# LMS7002M_RF2.net
KiCad netlist of a schematic drawn in Altium Designer
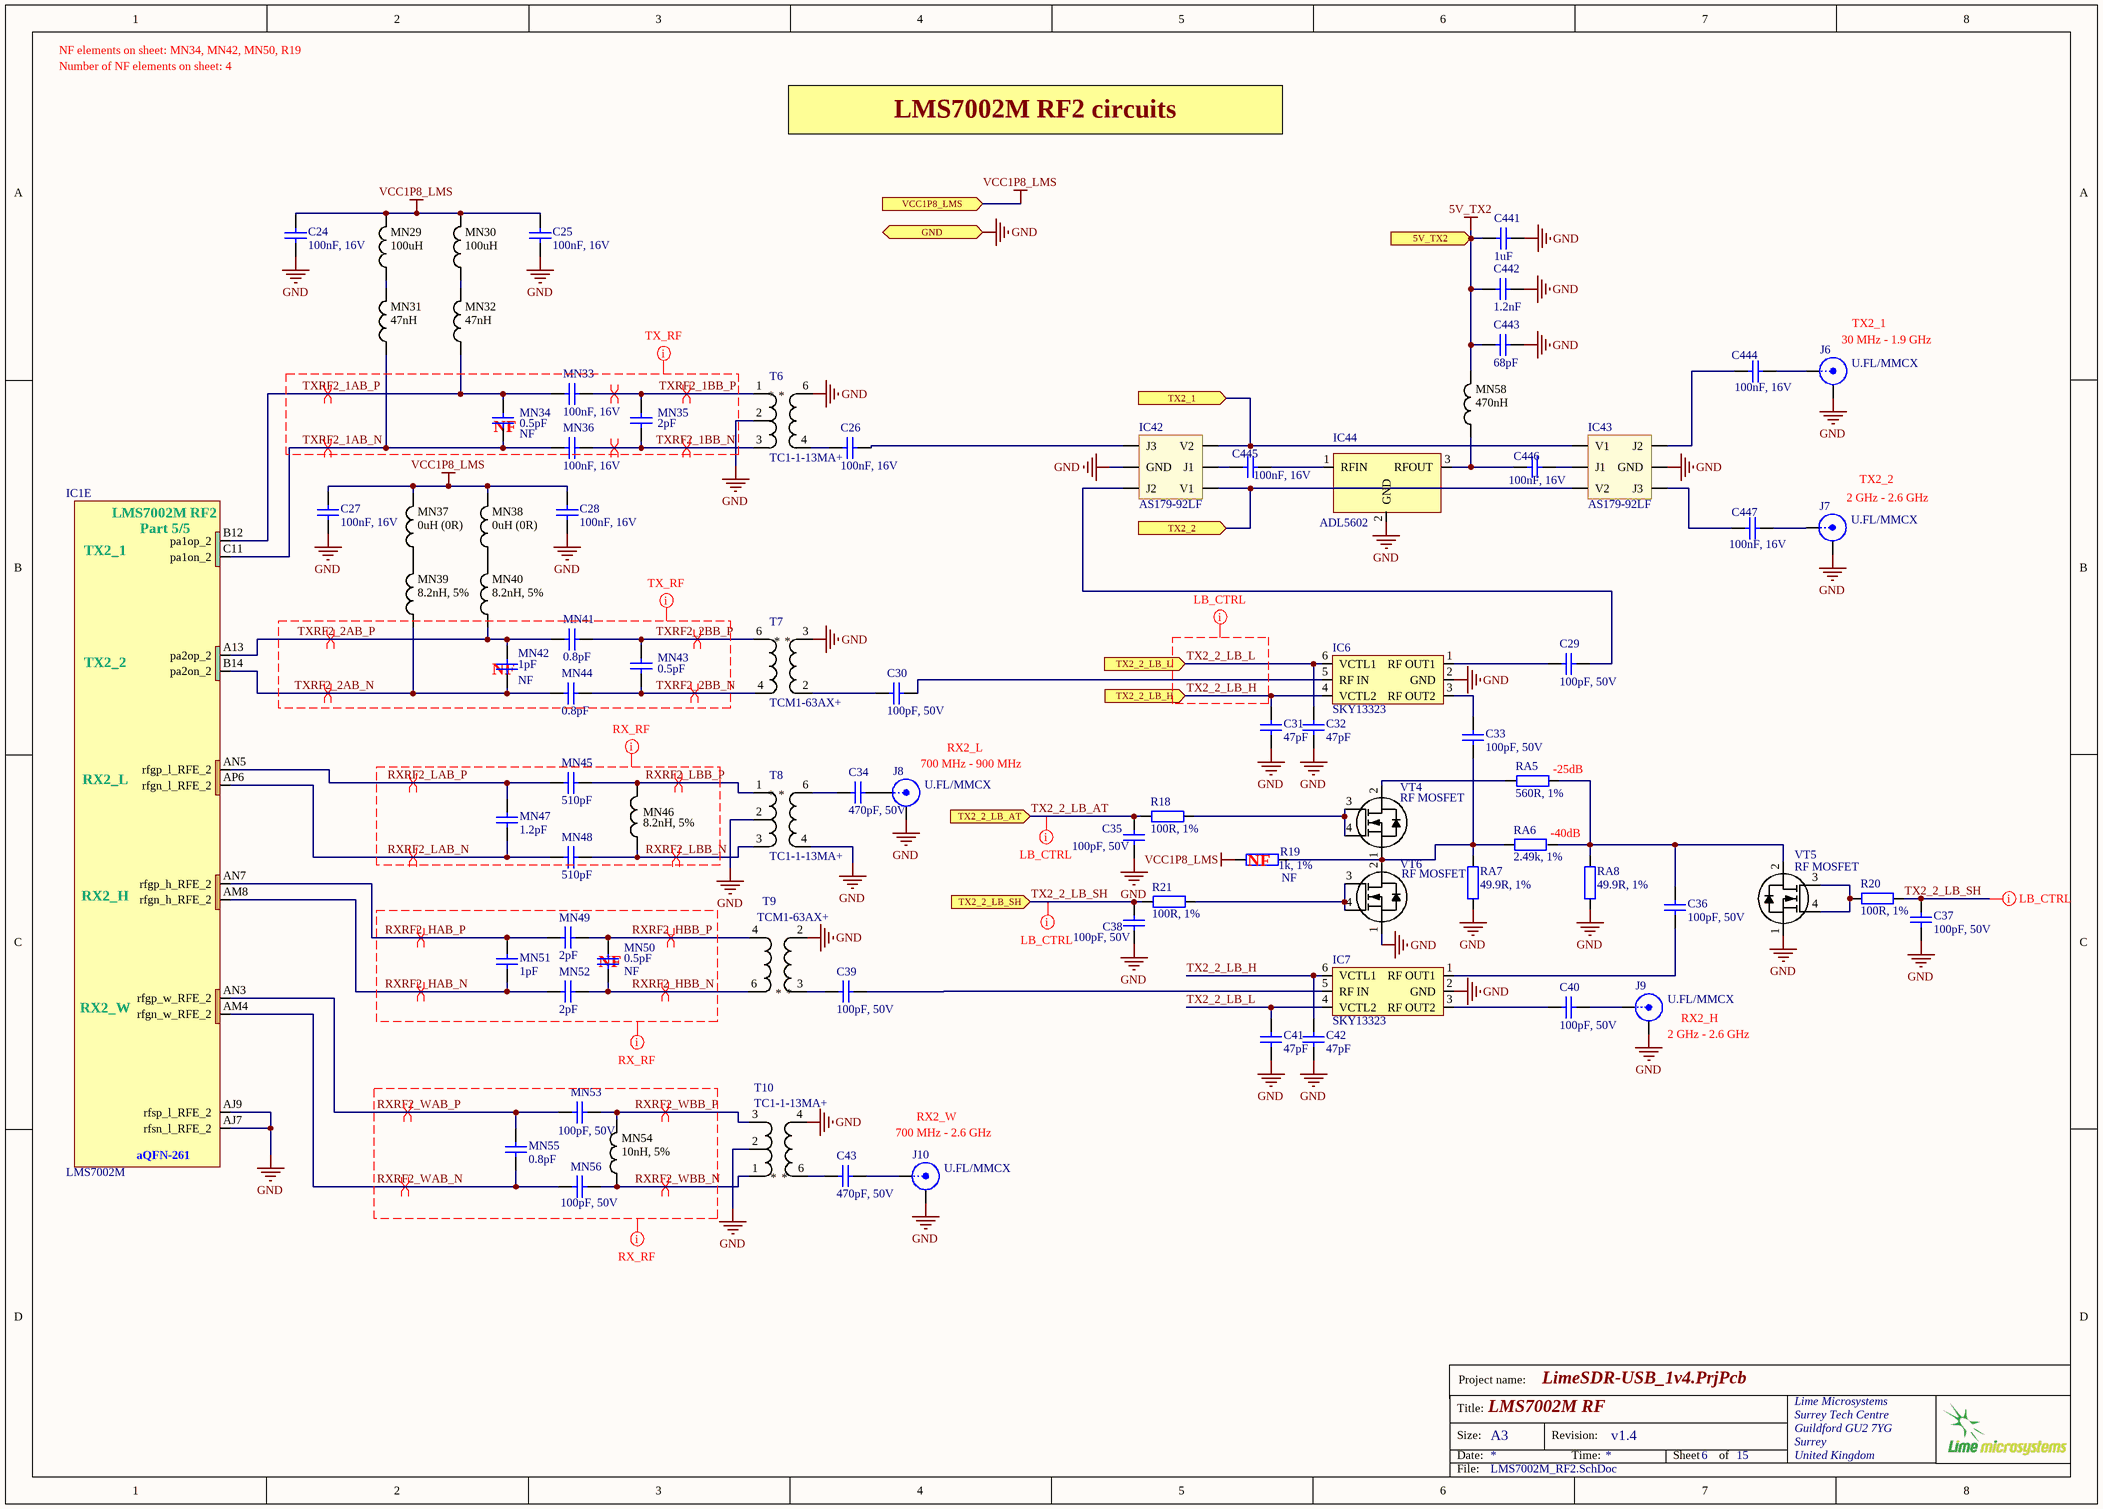
[diagram p0: LMS7002M_RF2.SchDoc]

(export (version "E")
  (design (tool "Eeschema 10.0.6"))
  (components
    (comp (ref "C24")
      (value "100nF, 16V")
      (footprint "CAP0402")
      (fields
        (field (name "MANUFACTURER") "Murata Electronics")
        (field (name "TOLERANCE") "10 %")
        (field (name "MANUFACTURER PART NUMBER") "GRM155R71C104KA88D")
      )
      (libsource (lib "LimeMicroAltiumLib_schLib") (part "Cap_0402"))
    )
    (comp (ref "C25")
      (value "100nF, 16V")
      (footprint "CAP0402")
      (fields
        (field (name "MANUFACTURER") "Murata Electronics")
        (field (name "TOLERANCE") "10 %")
        (field (name "MANUFACTURER PART NUMBER") "GRM155R71C104KA88D")
      )
      (libsource (lib "LimeMicroAltiumLib_schLib") (part "Cap_0402"))
    )
    (comp (ref "C26")
      (value "100nF, 16V")
      (footprint "CAP0402")
      (fields
        (field (name "MANUFACTURER") "Murata Electronics")
        (field (name "TOLERANCE") "10 %")
        (field (name "MANUFACTURER PART NUMBER") "GRM155R71C104KA88D")
      )
      (libsource (lib "LimeMicroAltiumLib_schLib") (part "Cap_0402"))
    )
    (comp (ref "C27")
      (value "100nF, 16V")
      (footprint "CAP0402")
      (fields
        (field (name "MANUFACTURER") "Murata Electronics")
        (field (name "TOLERANCE") "10 %")
        (field (name "MANUFACTURER PART NUMBER") "GRM155R71C104KA88D")
      )
      (libsource (lib "LimeMicroAltiumLib_schLib") (part "Cap_0402"))
    )
    (comp (ref "C28")
      (value "100nF, 16V")
      (footprint "CAP0402")
      (fields
        (field (name "MANUFACTURER") "Murata Electronics")
        (field (name "TOLERANCE") "10 %")
        (field (name "MANUFACTURER PART NUMBER") "GRM155R71C104KA88D")
      )
      (libsource (lib "LimeMicroAltiumLib_schLib") (part "Cap_0402"))
    )
    (comp (ref "C29")
      (value "100pF, 50V")
      (footprint "CAP0402")
      (fields (field (name "TOLERANCE") "±5%") (field (name "MANUFACTURER") "Yageo"))
      (libsource (lib "LimeMicroAltiumLib_schLib") (part "Cap_0402"))
    )
    (comp (ref "C30")
      (value "100pF, 50V")
      (footprint "CAP0402")
      (fields (field (name "TOLERANCE") "±5%") (field (name "MANUFACTURER") "Yageo"))
      (libsource (lib "LimeMicroAltiumLib_schLib") (part "Cap_0402"))
    )
    (comp (ref "C31")
      (value "47pF")
      (footprint "CAP0402")
      (fields (field (name "TOLERANCE") "±1%") (field (name "MANUFACTURER") "TDK Corporation"))
      (libsource (lib "LimeMicroAltiumLib_schLib") (part "Cap_0402"))
    )
    (comp (ref "C32")
      (value "47pF")
      (footprint "CAP0402")
      (fields (field (name "TOLERANCE") "±1%") (field (name "MANUFACTURER") "TDK Corporation"))
      (libsource (lib "LimeMicroAltiumLib_schLib") (part "Cap_0402"))
    )
    (comp (ref "C33")
      (value "100pF, 50V")
      (footprint "CAP0402")
      (fields (field (name "TOLERANCE") "±5%") (field (name "MANUFACTURER") "Yageo"))
      (libsource (lib "LimeMicroAltiumLib_schLib") (part "Cap_0402"))
    )
    (comp (ref "C34")
      (value "470pF, 50V")
      (footprint "CAP0402")
      (fields
        (field (name "MANUFACTURER PART NUMBER") "C1005C0G1H471J050BA")
        (field (name "TOLERANCE") "±5%")
        (field (name "MANUFACTURER") "TDK Corporation")
      )
      (libsource (lib "LimeMicroAltiumLib_schLib") (part "Cap_0402"))
    )
    (comp (ref "C35")
      (value "100pF, 50V")
      (footprint "CAP0402")
      (fields (field (name "TOLERANCE") "±5%") (field (name "MANUFACTURER") "Yageo"))
      (libsource (lib "LimeMicroAltiumLib_schLib") (part "Cap_0402"))
    )
    (comp (ref "C36")
      (value "100pF, 50V")
      (footprint "CAP0402")
      (fields (field (name "TOLERANCE") "±5%") (field (name "MANUFACTURER") "Yageo"))
      (libsource (lib "LimeMicroAltiumLib_schLib") (part "Cap_0402"))
    )
    (comp (ref "C37")
      (value "100pF, 50V")
      (footprint "CAP0402")
      (fields (field (name "TOLERANCE") "±5%") (field (name "MANUFACTURER") "Yageo"))
      (libsource (lib "LimeMicroAltiumLib_schLib") (part "Cap_0402"))
    )
    (comp (ref "C38")
      (value "100pF, 50V")
      (footprint "CAP0402")
      (fields (field (name "TOLERANCE") "±5%") (field (name "MANUFACTURER") "Yageo"))
      (libsource (lib "LimeMicroAltiumLib_schLib") (part "Cap_0402"))
    )
    (comp (ref "C39")
      (value "100pF, 50V")
      (footprint "CAP0402")
      (fields (field (name "TOLERANCE") "±5%") (field (name "MANUFACTURER") "Yageo"))
      (libsource (lib "LimeMicroAltiumLib_schLib") (part "Cap_0402"))
    )
    (comp (ref "C40")
      (value "100pF, 50V")
      (footprint "CAP0402")
      (fields (field (name "TOLERANCE") "±5%") (field (name "MANUFACTURER") "Yageo"))
      (libsource (lib "LimeMicroAltiumLib_schLib") (part "Cap_0402"))
    )
    (comp (ref "C41")
      (value "47pF")
      (footprint "CAP0402")
      (fields (field (name "TOLERANCE") "±1%") (field (name "MANUFACTURER") "TDK Corporation"))
      (libsource (lib "LimeMicroAltiumLib_schLib") (part "Cap_0402"))
    )
    (comp (ref "C42")
      (value "47pF")
      (footprint "CAP0402")
      (fields (field (name "TOLERANCE") "±1%") (field (name "MANUFACTURER") "TDK Corporation"))
      (libsource (lib "LimeMicroAltiumLib_schLib") (part "Cap_0402"))
    )
    (comp (ref "C43")
      (value "470pF, 50V")
      (footprint "CAP0402")
      (fields
        (field (name "MANUFACTURER PART NUMBER") "C1005C0G1H471J050BA")
        (field (name "TOLERANCE") "±5%")
        (field (name "MANUFACTURER") "TDK Corporation")
      )
      (libsource (lib "LimeMicroAltiumLib_schLib") (part "Cap_0402"))
    )
    (comp (ref "C441")
      (value "1uF")
      (footprint "CAP0402")
      (fields
        (field (name "MANUFACTURER") "Murata Electronics")
        (field (name "TOLERANCE") "10 %")
        (field (name "MANUFACTURER PART NUMBER") "GRM155R71C104KA88D")
      )
      (libsource (lib "LimeMicroAltiumLib_schLib") (part "Cap_0402"))
    )
    (comp (ref "C442")
      (value "1.2nF")
      (footprint "CAP0402")
      (fields
        (field (name "MANUFACTURER") "Murata Electronics")
        (field (name "TOLERANCE") "10 %")
        (field (name "MANUFACTURER PART NUMBER") "GRM155R71C104KA88D")
      )
      (libsource (lib "LimeMicroAltiumLib_schLib") (part "Cap_0402"))
    )
    (comp (ref "C443")
      (value "68pF")
      (footprint "CAP0402")
      (fields
        (field (name "MANUFACTURER") "Murata Electronics")
        (field (name "TOLERANCE") "10 %")
        (field (name "MANUFACTURER PART NUMBER") "GRM155R71C104KA88D")
      )
      (libsource (lib "LimeMicroAltiumLib_schLib") (part "Cap_0402"))
    )
    (comp (ref "C444")
      (value "100nF, 16V")
      (footprint "CAP0402")
      (fields
        (field (name "MANUFACTURER") "Murata Electronics")
        (field (name "TOLERANCE") "10 %")
        (field (name "MANUFACTURER PART NUMBER") "GRM155R71C104KA88D")
      )
      (libsource (lib "LimeMicroAltiumLib_schLib") (part "Cap_0402"))
    )
    (comp (ref "C445")
      (value "100nF, 16V")
      (footprint "CAP0402")
      (fields
        (field (name "MANUFACTURER") "Murata Electronics")
        (field (name "TOLERANCE") "10 %")
        (field (name "MANUFACTURER PART NUMBER") "GRM155R71C104KA88D")
      )
      (libsource (lib "LimeMicroAltiumLib_schLib") (part "Cap_0402"))
    )
    (comp (ref "C446")
      (value "100nF, 16V")
      (footprint "CAP0402")
      (fields
        (field (name "MANUFACTURER") "Murata Electronics")
        (field (name "TOLERANCE") "10 %")
        (field (name "MANUFACTURER PART NUMBER") "GRM155R71C104KA88D")
      )
      (libsource (lib "LimeMicroAltiumLib_schLib") (part "Cap_0402"))
    )
    (comp (ref "C447")
      (value "100nF, 16V")
      (footprint "CAP0402")
      (fields
        (field (name "MANUFACTURER") "Murata Electronics")
        (field (name "TOLERANCE") "10 %")
        (field (name "MANUFACTURER PART NUMBER") "GRM155R71C104KA88D")
      )
      (libsource (lib "LimeMicroAltiumLib_schLib") (part "Cap_0402"))
    )
    (comp (ref "IC1")
      (value "LMS7002M")
      (footprint "LMS7002M_v3")
      (fields (field (name "MANUFACTURER") "Lime Microsystems"))
      (libsource (lib "LimeMicroAltiumLib_schLib") (part "LMS7002M"))
    )
    (comp (ref "IC6")
      (value "SKY13323")
      (footprint "SKY13323-378LF")
      (description "SKY13323-378LF: 0.1-3.0 GHz GaAs SPDT Switch")
      (fields (field (name "MANUFACTURER") "Skyworks Solutions Inc."))
      (libsource (lib "LimeMicroAltiumLib_schLib") (part "SKY13323"))
    )
    (comp (ref "IC7")
      (value "SKY13323")
      (footprint "SKY13323-378LF")
      (description "SKY13323-378LF: 0.1-3.0 GHz GaAs SPDT Switch")
      (fields (field (name "MANUFACTURER") "Skyworks Solutions Inc."))
      (libsource (lib "LimeMicroAltiumLib_schLib") (part "SKY13323"))
    )
    (comp (ref "IC42") (value "AS179-92LF") (footprint "SC-70") (libsource (lib "") (part "AS179-92LF_1")))
    (comp (ref "IC43")
      (value "AS179-92LF")
      (footprint "SC-70")
      (libsource (lib "LimeMicroAltiumLib_schLib") (part "AS179-92LF"))
    )
    (comp (ref "IC44")
      (value "ADL5602")
      (footprint "SOT-89-ADI-RK-3_M")
      (description "50 MHz to 4.0 GHz RF/IF Gain Block")
      (fields
        (field (name "MANUFACTURER") "Analog Devices Inc.")
        (field (name "MANUFACTURER PART NUMBER") "ADL5602ARKZ-R7")
      )
      (libsource (lib "LimeMicroAltiumLib_schLib") (part "ADL5602"))
    )
    (comp (ref "J6")
      (value "U.FL/MMCX")
      (footprint "MMCX_UFL_conn_u")
      (description "CONN UMC RCPT STR 50 OHM SMD")
      (fields (field (name "MANUFACTURER") "Molex, LLC"))
      (libsource (lib "LimeMicroAltiumLib_schLib") (part "RF_IF_connector"))
    )
    (comp (ref "J7")
      (value "U.FL/MMCX")
      (footprint "MMCX_UFL_conn_u")
      (description "CONN UMC RCPT STR 50 OHM SMD")
      (fields (field (name "MANUFACTURER") "Molex, LLC"))
      (libsource (lib "LimeMicroAltiumLib_schLib") (part "RF_IF_connector"))
    )
    (comp (ref "J8")
      (value "U.FL/MMCX")
      (footprint "MMCX_UFL_conn_u")
      (description "CONN UMC RCPT STR 50 OHM SMD")
      (fields (field (name "MANUFACTURER") "Molex, LLC"))
      (libsource (lib "LimeMicroAltiumLib_schLib") (part "RF_IF_connector"))
    )
    (comp (ref "J9")
      (value "U.FL/MMCX")
      (footprint "MMCX_UFL_conn_u")
      (description "CONN UMC RCPT STR 50 OHM SMD")
      (fields (field (name "MANUFACTURER") "Molex, LLC"))
      (libsource (lib "LimeMicroAltiumLib_schLib") (part "RF_IF_connector"))
    )
    (comp (ref "J10")
      (value "U.FL/MMCX")
      (footprint "MMCX_UFL_conn_u")
      (description "CONN UMC RCPT STR 50 OHM SMD")
      (fields (field (name "MANUFACTURER") "Molex, LLC"))
      (libsource (lib "LimeMicroAltiumLib_schLib") (part "RF_IF_connector"))
    )
    (comp (ref "MN29")
      (value "100uH")
      (footprint "RES0805")
      (fields
        (field (name "TOLERANCE") "±10%")
        (field (name "MANUFACTURER") "TDK Corporation")
        (field (name "MANUFACTURER PART NUMBER") "MLF2012C101KT000")
      )
      (libsource (lib "LimeMicroAltiumLib_schLib") (part "Inductor_0603"))
    )
    (comp (ref "MN30")
      (value "100uH")
      (footprint "RES0805")
      (fields
        (field (name "TOLERANCE") "±10%")
        (field (name "MANUFACTURER") "TDK Corporation")
        (field (name "MANUFACTURER PART NUMBER") "MLF2012C101KT000")
      )
      (libsource (lib "LimeMicroAltiumLib_schLib") (part "Inductor_0603"))
    )
    (comp (ref "MN31")
      (value "47nH")
      (footprint "RES0402")
      (fields
        (field (name "MANUFACTURER") "COILCRAFT")
        (field (name "MANUFACTURER PART NUMBER") "0402HP-47NXJLU")
      )
      (libsource (lib "LimeMicroAltiumLib_schLib") (part "Inductor_0603"))
    )
    (comp (ref "MN32")
      (value "47nH")
      (footprint "RES0402")
      (fields
        (field (name "MANUFACTURER") "COILCRAFT")
        (field (name "MANUFACTURER PART NUMBER") "0402HP-47NXJLU")
      )
      (libsource (lib "LimeMicroAltiumLib_schLib") (part "Inductor_0603"))
    )
    (comp (ref "MN33")
      (value "100nF, 16V")
      (footprint "CAP0402")
      (fields
        (field (name "MANUFACTURER") "Murata Electronics")
        (field (name "TOLERANCE") "10 %")
        (field (name "MANUFACTURER PART NUMBER") "GRM155R71C104KA88D")
      )
      (libsource (lib "LimeMicroAltiumLib_schLib") (part "Cap_0402"))
    )
    (comp (ref "MN34")
      (value "0.5pF")
      (footprint "CAP0402")
      (fields
        (field (name "ASSEMBLY INFO") "NF")
        (field (name "TOLERANCE") "±0.25pF")
        (field (name "MANUFACTURER") "Yageo")
      )
      (libsource (lib "LimeMicroAltiumLib_schLib") (part "Cap_0402"))
    )
    (comp (ref "MN35")
      (value "2pF")
      (footprint "CAP0402")
      (fields (field (name "MANUFACTURER PART NUMBER") "04025U2R0BAT2A") (field (name "MANUFACTURER") "AVX"))
      (libsource (lib "LimeMicroAltiumLib_schLib") (part "Cap_0402"))
    )
    (comp (ref "MN36")
      (value "100nF, 16V")
      (footprint "CAP0402")
      (fields
        (field (name "MANUFACTURER") "Murata Electronics")
        (field (name "TOLERANCE") "10 %")
        (field (name "MANUFACTURER PART NUMBER") "GRM155R71C104KA88D")
      )
      (libsource (lib "LimeMicroAltiumLib_schLib") (part "Cap_0402"))
    )
    (comp (ref "MN37")
      (value "0uH (0R)")
      (footprint "RES0805")
      (fields (field (name "MANUFACTURER") "BOURNS"))
      (libsource (lib "LimeMicroAltiumLib_schLib") (part "Inductor_0603"))
    )
    (comp (ref "MN38")
      (value "0uH (0R)")
      (footprint "RES0805")
      (fields (field (name "MANUFACTURER") "BOURNS"))
      (libsource (lib "LimeMicroAltiumLib_schLib") (part "Inductor_0603"))
    )
    (comp (ref "MN39")
      (value "8.2nH, 5%")
      (footprint "RES0402")
      (fields (field (name "MANUFACTURER") "COILCRAFT"))
      (libsource (lib "LimeMicroAltiumLib_schLib") (part "Inductor_0603"))
    )
    (comp (ref "MN40")
      (value "8.2nH, 5%")
      (footprint "RES0402")
      (fields (field (name "MANUFACTURER") "COILCRAFT"))
      (libsource (lib "LimeMicroAltiumLib_schLib") (part "Inductor_0603"))
    )
    (comp (ref "MN41")
      (value "0.8pF")
      (footprint "CAP0402")
      (fields
        (field (name "TOLERANCE") "±0.1pF")
        (field (name "MANUFACTURER") "Murata Electronics North America")
        (field (name "MANUFACTURER PART NUMBER") "GRM1555C1HR80BA01D")
      )
      (libsource (lib "LimeMicroAltiumLib_schLib") (part "Cap_0402"))
    )
    (comp (ref "MN42")
      (value "1pF")
      (footprint "CAP0402")
      (fields
        (field (name "ASSEMBLY INFO") "NF")
        (field (name "MANUFACTURER") "TDK Corporation")
        (field (name "TOLERANCE") "±0.1pF")
      )
      (libsource (lib "LimeMicroAltiumLib_schLib") (part "Cap_0402"))
    )
    (comp (ref "MN43")
      (value "0.5pF")
      (footprint "CAP0402")
      (fields (field (name "TOLERANCE") "±0.25pF") (field (name "MANUFACTURER") "Yageo"))
      (libsource (lib "LimeMicroAltiumLib_schLib") (part "Cap_0402"))
    )
    (comp (ref "MN44")
      (value "0.8pF")
      (footprint "CAP0402")
      (fields
        (field (name "TOLERANCE") "±0.1pF")
        (field (name "MANUFACTURER") "Murata Electronics North America")
        (field (name "MANUFACTURER PART NUMBER") "GRM1555C1HR80BA01D")
      )
      (libsource (lib "LimeMicroAltiumLib_schLib") (part "Cap_0402"))
    )
    (comp (ref "MN45")
      (value "510pF")
      (footprint "CAP0402")
      (fields
        (field (name "TOLERANCE") "±5%")
        (field (name "MANUFACTURER") "Murata Electronics North America")
        (field (name "MANUFACTURER PART NUMBER") "GRM1555C1H511JA01D")
      )
      (libsource (lib "LimeMicroAltiumLib_schLib") (part "Cap_0402"))
    )
    (comp (ref "MN46")
      (value "8.2nH, 5%")
      (footprint "RES0402")
      (fields (field (name "MANUFACTURER") "COILCRAFT"))
      (libsource (lib "LimeMicroAltiumLib_schLib") (part "Inductor_0603"))
    )
    (comp (ref "MN47")
      (value "1.2pF")
      (footprint "CAP0402")
      (fields
        (field (name "MANUFACTURER") "Murata Electronics North America")
        (field (name "MANUFACTURER PART NUMBER") "GRM1555C1H1R2CA01D")
        (field (name "TOLERANCE") "±0.25pF")
      )
      (libsource (lib "LimeMicroAltiumLib_schLib") (part "Cap_0402"))
    )
    (comp (ref "MN48")
      (value "510pF")
      (footprint "CAP0402")
      (fields
        (field (name "TOLERANCE") "±5%")
        (field (name "MANUFACTURER") "Murata Electronics North America")
        (field (name "MANUFACTURER PART NUMBER") "GRM1555C1H511JA01D")
      )
      (libsource (lib "LimeMicroAltiumLib_schLib") (part "Cap_0402"))
    )
    (comp (ref "MN49")
      (value "2pF")
      (footprint "CAP0402")
      (fields (field (name "MANUFACTURER PART NUMBER") "04025U2R0BAT2A") (field (name "MANUFACTURER") "AVX"))
      (libsource (lib "LimeMicroAltiumLib_schLib") (part "Cap_0402"))
    )
    (comp (ref "MN50")
      (value "0.5pF")
      (footprint "CAP0402")
      (fields
        (field (name "ASSEMBLY INFO") "NF")
        (field (name "TOLERANCE") "±0.25pF")
        (field (name "MANUFACTURER") "Yageo")
      )
      (libsource (lib "LimeMicroAltiumLib_schLib") (part "Cap_0402"))
    )
    (comp (ref "MN51")
      (value "1pF")
      (footprint "CAP0402")
      (fields (field (name "MANUFACTURER") "TDK Corporation") (field (name "TOLERANCE") "±0.1pF"))
      (libsource (lib "LimeMicroAltiumLib_schLib") (part "Cap_0402"))
    )
    (comp (ref "MN52")
      (value "2pF")
      (footprint "CAP0402")
      (fields (field (name "MANUFACTURER PART NUMBER") "04025U2R0BAT2A") (field (name "MANUFACTURER") "AVX"))
      (libsource (lib "LimeMicroAltiumLib_schLib") (part "Cap_0402"))
    )
    (comp (ref "MN53")
      (value "100pF, 50V")
      (footprint "CAP0402")
      (fields (field (name "TOLERANCE") "±5%") (field (name "MANUFACTURER") "Yageo"))
      (libsource (lib "LimeMicroAltiumLib_schLib") (part "Cap_0402"))
    )
    (comp (ref "MN54")
      (value "10nH, 5%")
      (footprint "RES0402")
      (fields (field (name "MANUFACTURER") "COILCRAFT"))
      (libsource (lib "LimeMicroAltiumLib_schLib") (part "Inductor_0603"))
    )
    (comp (ref "MN55")
      (value "0.8pF")
      (footprint "CAP0402")
      (fields
        (field (name "TOLERANCE") "±0.1pF")
        (field (name "MANUFACTURER") "Murata Electronics North America")
        (field (name "MANUFACTURER PART NUMBER") "GRM1555C1HR80BA01D")
      )
      (libsource (lib "LimeMicroAltiumLib_schLib") (part "Cap_0402"))
    )
    (comp (ref "MN56")
      (value "100pF, 50V")
      (footprint "CAP0402")
      (fields (field (name "TOLERANCE") "±5%") (field (name "MANUFACTURER") "Yageo"))
      (libsource (lib "LimeMicroAltiumLib_schLib") (part "Cap_0402"))
    )
    (comp (ref "MN58")
      (value "470nH")
      (footprint "RES0402")
      (fields
        (field (name "MANUFACTURER") "COILCRAFT")
        (field (name "MANUFACTURER PART NUMBER") "0402HP-47NXJLU")
      )
      (libsource (lib "LimeMicroAltiumLib_schLib") (part "Inductor_0603"))
    )
    (comp (ref "R18")
      (value "100R, 1%")
      (footprint "RES0402")
      (fields (field (name "TOLERANCE") "±1%") (field (name "MANUFACTURER") "Stackpole Electronics Inc."))
      (libsource (lib "LimeFPGAboard_schLib") (part "Res_0402"))
    )
    (comp (ref "R19")
      (value "1k, 1%")
      (footprint "RES0402")
      (fields
        (field (name "ASSEMBLY INFO") "NF")
        (field (name "MANUFACTURER") "Stackpole Electronics Inc")
        (field (name "TOLERANCE") "±1%")
      )
      (libsource (lib "LimeMicroAltiumLib_schLib") (part "Res_0402"))
    )
    (comp (ref "R20")
      (value "100R, 1%")
      (footprint "RES0402")
      (fields (field (name "TOLERANCE") "±1%") (field (name "MANUFACTURER") "Stackpole Electronics Inc."))
      (libsource (lib "LimeFPGAboard_schLib") (part "Res_0402"))
    )
    (comp (ref "R21")
      (value "100R, 1%")
      (footprint "RES0402")
      (fields (field (name "TOLERANCE") "±1%") (field (name "MANUFACTURER") "Stackpole Electronics Inc."))
      (libsource (lib "LimeFPGAboard_schLib") (part "Res_0402"))
    )
    (comp (ref "RA5")
      (value "560R, 1%")
      (footprint "RES0402")
      (fields
        (field (name "MANUFACTURER PART NUMBER") "CRCW0402560RFKED")
        (field (name "TOLERANCE") "±1%")
        (field (name "MANUFACTURER") "Vishay Dale")
      )
      (libsource (lib "LimeMicroAltiumLib_schLib") (part "Res_0402"))
    )
    (comp (ref "RA6")
      (value "2.49k, 1%")
      (footprint "RES0402")
      (fields
        (field (name "TOLERANCE") "±1%")
        (field (name "MANUFACTURER PART NUMBER") "RC0402FR-072K49L")
        (field (name "MANUFACTURER") "Yageo")
      )
      (libsource (lib "LimeMicroAltiumLib_schLib") (part "Res_0402"))
    )
    (comp (ref "RA7")
      (value "49.9R, 1%")
      (footprint "RES0402")
      (fields
        (field (name "TOLERANCE") "±1%")
        (field (name "MANUFACTURER") "Samsung Electro-Mechanics America, Inc.")
        (field (name "MANUFACTURER PART NUMBER") "RC1005F49R9CS")
      )
      (libsource (lib "LimeMicroAltiumLib_schLib") (part "Res_0402"))
    )
    (comp (ref "RA8")
      (value "49.9R, 1%")
      (footprint "RES0402")
      (fields
        (field (name "TOLERANCE") "±1%")
        (field (name "MANUFACTURER") "Samsung Electro-Mechanics America, Inc.")
        (field (name "MANUFACTURER PART NUMBER") "RC1005F49R9CS")
      )
      (libsource (lib "LimeMicroAltiumLib_schLib") (part "Res_0402"))
    )
    (comp (ref "T6")
      (value "TC1-1-13MA+")
      (footprint "TC1-1-13MA+_v2")
      (fields (field (name "MANUFACTURER") "Mini-Circuits"))
      (libsource (lib "LimeMicroAltiumLib_schLib") (part "Balun"))
    )
    (comp (ref "T7")
      (value "TCM1-63AX+")
      (footprint "TCM1-63AX+_v2")
      (fields (field (name "MANUFACTURER") "Mini-circuits"))
      (libsource (lib "LimeMicroAltiumLib_schLib") (part "Balun_v2"))
    )
    (comp (ref "T8")
      (value "TC1-1-13MA+")
      (footprint "TC1-1-13MA+_v2")
      (fields (field (name "MANUFACTURER") "Mini-Circuits"))
      (libsource (lib "LimeMicroAltiumLib_schLib") (part "Balun"))
    )
    (comp (ref "T9")
      (value "TCM1-63AX+")
      (footprint "TCM1-63AX+_v2")
      (fields (field (name "MANUFACTURER") "Mini-circuits"))
      (libsource (lib "") (part "Balun_v2_1"))
    )
    (comp (ref "T10")
      (value "TC1-1-13MA+")
      (footprint "TC1-1-13MA+_v2")
      (fields (field (name "MANUFACTURER") "Mini-Circuits"))
      (libsource (lib "") (part "Balun_1"))
    )
    (comp (ref "VT4")
      (value "RF MOSFET")
      (footprint "BF1105R_SOT143R4")
      (fields (field (name "MANUFACTURER") "NXP Semiconductors"))
      (libsource (lib "LimeMicroAltiumLib_schLib") (part "BF1105R,215"))
    )
    (comp (ref "VT5")
      (value "RF MOSFET")
      (footprint "BF1105R_SOT143R4")
      (fields (field (name "MANUFACTURER") "NXP Semiconductors"))
      (libsource (lib "LimeMicroAltiumLib_schLib") (part "BF1105R,215"))
    )
    (comp (ref "VT6")
      (value "RF MOSFET")
      (footprint "BF1105R_SOT143R4")
      (fields (field (name "MANUFACTURER") "NXP Semiconductors"))
      (libsource (lib "LimeMicroAltiumLib_schLib") (part "BF1105R,215"))
    )
  )
  (nets
    (net (code "1") (name "/RXRF2_HAB_N") (class "Default")
      (node (ref "IC1") (pin "AM8") (pinfunction "rfgn_h_RFE_2_AM8") (pintype "passive"))
      (node (ref "MN51") (pin "1") (pinfunction "1_1") (pintype "passive"))
      (node (ref "MN52") (pin "2") (pinfunction "2_2") (pintype "passive"))
    )
    (net (code "2") (name "/RXRF2_HAB_P") (class "Default")
      (node (ref "IC1") (pin "AN7") (pinfunction "rfgp_h_RFE_2_AN7") (pintype "passive"))
      (node (ref "MN49") (pin "2") (pinfunction "2_2") (pintype "passive"))
      (node (ref "MN51") (pin "2") (pinfunction "2_2") (pintype "passive"))
    )
    (net (code "3") (name "/RXRF2_HBB_N") (class "Default")
      (node (ref "MN50") (pin "1") (pinfunction "1_1") (pintype "passive"))
      (node (ref "MN52") (pin "1") (pinfunction "1_1") (pintype "passive"))
      (node (ref "T9") (pin "6") (pinfunction "6_6") (pintype "passive"))
    )
    (net (code "4") (name "/RXRF2_HBB_P") (class "Default")
      (node (ref "MN49") (pin "1") (pinfunction "1_1") (pintype "passive"))
      (node (ref "MN50") (pin "2") (pinfunction "2_2") (pintype "passive"))
      (node (ref "T9") (pin "4") (pinfunction "4_4") (pintype "passive"))
    )
    (net (code "5") (name "/RXRF2_LAB_N") (class "Default")
      (node (ref "IC1") (pin "AP6") (pinfunction "rfgn_l_RFE_2_AP6") (pintype "passive"))
      (node (ref "MN47") (pin "1") (pinfunction "1_1") (pintype "passive"))
      (node (ref "MN48") (pin "2") (pinfunction "2_2") (pintype "passive"))
    )
    (net (code "6") (name "/RXRF2_LAB_P") (class "Default")
      (node (ref "IC1") (pin "AN5") (pinfunction "rfgp_l_RFE_2_AN5") (pintype "passive"))
      (node (ref "MN45") (pin "2") (pinfunction "2_2") (pintype "passive"))
      (node (ref "MN47") (pin "2") (pinfunction "2_2") (pintype "passive"))
    )
    (net (code "7") (name "/RXRF2_LBB_N") (class "Default")
      (node (ref "MN46") (pin "1") (pinfunction "1_1") (pintype "passive"))
      (node (ref "MN48") (pin "1") (pinfunction "1_1") (pintype "passive"))
      (node (ref "T8") (pin "3") (pinfunction "3_3") (pintype "passive"))
    )
    (net (code "8") (name "/RXRF2_LBB_P") (class "Default")
      (node (ref "MN45") (pin "1") (pinfunction "1_1") (pintype "passive"))
      (node (ref "MN46") (pin "2") (pinfunction "2_2") (pintype "passive"))
      (node (ref "T8") (pin "1") (pinfunction "1_1") (pintype "passive"))
    )
    (net (code "9") (name "/RXRF2_WAB_N") (class "Default")
      (node (ref "IC1") (pin "AM4") (pinfunction "rfgn_w_RFE_2_AM4") (pintype "passive"))
      (node (ref "MN55") (pin "2") (pinfunction "2_2") (pintype "passive"))
      (node (ref "MN56") (pin "2") (pinfunction "2_2") (pintype "passive"))
    )
    (net (code "10") (name "/RXRF2_WAB_P") (class "Default")
      (node (ref "IC1") (pin "AN3") (pinfunction "rfgp_w_RFE_2_AN3") (pintype "passive"))
      (node (ref "MN53") (pin "2") (pinfunction "2_2") (pintype "passive"))
      (node (ref "MN55") (pin "1") (pinfunction "1_1") (pintype "passive"))
    )
    (net (code "11") (name "/RXRF2_WBB_N") (class "Default")
      (node (ref "MN54") (pin "1") (pinfunction "1_1") (pintype "passive"))
      (node (ref "MN56") (pin "1") (pinfunction "1_1") (pintype "passive"))
      (node (ref "T10") (pin "1") (pinfunction "1_1") (pintype "passive"))
    )
    (net (code "12") (name "/RXRF2_WBB_P") (class "Default")
      (node (ref "MN53") (pin "1") (pinfunction "1_1") (pintype "passive"))
      (node (ref "MN54") (pin "2") (pinfunction "2_2") (pintype "passive"))
      (node (ref "T10") (pin "3") (pinfunction "3_3") (pintype "passive"))
    )
    (net (code "13") (name "/TX2_1") (class "Default")
      (node (ref "IC42") (pin "6") (pinfunction "V2_6") (pintype "passive"))
      (node (ref "IC43") (pin "4") (pinfunction "V1_4") (pintype "passive"))
    )
    (net (code "14") (name "/TX2_2") (class "Default")
      (node (ref "IC42") (pin "4") (pinfunction "V1_4") (pintype "passive"))
      (node (ref "IC43") (pin "6") (pinfunction "V2_6") (pintype "passive"))
    )
    (net (code "15") (name "/TX2_2_LB_AT") (class "Default")
      (node (ref "C35") (pin "1") (pinfunction "1_1") (pintype "passive"))
      (node (ref "R18") (pin "2") (pinfunction "2_2") (pintype "passive"))
    )
    (net (code "16") (name "/TX2_2_LB_H") (class "Default")
      (node (ref "C31") (pin "2") (pinfunction "2_2") (pintype "passive"))
      (node (ref "C42") (pin "2") (pinfunction "2_2") (pintype "passive"))
      (node (ref "IC6") (pin "4") (pinfunction "VCTL2_4") (pintype "input"))
      (node (ref "IC7") (pin "6") (pinfunction "VCTL1_6") (pintype "input"))
    )
    (net (code "17") (name "/TX2_2_LB_L") (class "Default")
      (node (ref "C32") (pin "2") (pinfunction "2_2") (pintype "passive"))
      (node (ref "C41") (pin "2") (pinfunction "2_2") (pintype "passive"))
      (node (ref "IC6") (pin "6") (pinfunction "VCTL1_6") (pintype "input"))
      (node (ref "IC7") (pin "4") (pinfunction "VCTL2_4") (pintype "input"))
    )
    (net (code "18") (name "/TX2_2_LB_SH") (class "Default")
      (node (ref "C37") (pin "1") (pinfunction "1_1") (pintype "passive"))
      (node (ref "C38") (pin "1") (pinfunction "1_1") (pintype "passive"))
      (node (ref "R20") (pin "1") (pinfunction "1_1") (pintype "passive"))
      (node (ref "R21") (pin "2") (pinfunction "2_2") (pintype "passive"))
    )
    (net (code "19") (name "/TXRF2_1AB_N") (class "Default")
      (node (ref "IC1") (pin "C11") (pinfunction "pa1on_2_C11") (pintype "passive"))
      (node (ref "MN31") (pin "1") (pinfunction "1_1") (pintype "passive"))
      (node (ref "MN34") (pin "1") (pinfunction "1_1") (pintype "passive"))
      (node (ref "MN36") (pin "1") (pinfunction "1_1") (pintype "passive"))
    )
    (net (code "20") (name "/TXRF2_1AB_P") (class "Default")
      (node (ref "IC1") (pin "B12") (pinfunction "pa1op_2_B12") (pintype "passive"))
      (node (ref "MN32") (pin "1") (pinfunction "1_1") (pintype "passive"))
      (node (ref "MN33") (pin "2") (pinfunction "2_2") (pintype "passive"))
      (node (ref "MN34") (pin "2") (pinfunction "2_2") (pintype "passive"))
    )
    (net (code "21") (name "/TXRF2_1BB_N") (class "Default")
      (node (ref "MN35") (pin "1") (pinfunction "1_1") (pintype "passive"))
      (node (ref "MN36") (pin "2") (pinfunction "2_2") (pintype "passive"))
      (node (ref "T6") (pin "3") (pinfunction "3_3") (pintype "passive"))
    )
    (net (code "22") (name "/TXRF2_1BB_P") (class "Default")
      (node (ref "MN33") (pin "1") (pinfunction "1_1") (pintype "passive"))
      (node (ref "MN35") (pin "2") (pinfunction "2_2") (pintype "passive"))
      (node (ref "T6") (pin "1") (pinfunction "1_1") (pintype "passive"))
    )
    (net (code "23") (name "/TXRF2_2AB_N") (class "Default")
      (node (ref "IC1") (pin "B14") (pinfunction "pa2on_2_B14") (pintype "passive"))
      (node (ref "MN39") (pin "1") (pinfunction "1_1") (pintype "passive"))
      (node (ref "MN42") (pin "2") (pinfunction "2_2") (pintype "passive"))
      (node (ref "MN44") (pin "2") (pinfunction "2_2") (pintype "passive"))
    )
    (net (code "24") (name "/TXRF2_2AB_P") (class "Default")
      (node (ref "IC1") (pin "A13") (pinfunction "pa2op_2_A13") (pintype "passive"))
      (node (ref "MN40") (pin "1") (pinfunction "1_1") (pintype "passive"))
      (node (ref "MN41") (pin "2") (pinfunction "2_2") (pintype "passive"))
      (node (ref "MN42") (pin "1") (pinfunction "1_1") (pintype "passive"))
    )
    (net (code "25") (name "/TXRF2_2BB_N") (class "Default")
      (node (ref "MN43") (pin "1") (pinfunction "1_1") (pintype "passive"))
      (node (ref "MN44") (pin "1") (pinfunction "1_1") (pintype "passive"))
      (node (ref "T7") (pin "4") (pinfunction "4_4") (pintype "passive"))
    )
    (net (code "26") (name "/TXRF2_2BB_P") (class "Default")
      (node (ref "MN41") (pin "1") (pinfunction "1_1") (pintype "passive"))
      (node (ref "MN43") (pin "2") (pinfunction "2_2") (pintype "passive"))
      (node (ref "T7") (pin "6") (pinfunction "6_6") (pintype "passive"))
    )
    (net (code "27") (name "5V_TX2") (class "Default")
      (node (ref "C441") (pin "2") (pinfunction "2_2") (pintype "passive"))
      (node (ref "C442") (pin "2") (pinfunction "2_2") (pintype "passive"))
      (node (ref "C443") (pin "2") (pinfunction "2_2") (pintype "passive"))
      (node (ref "MN58") (pin "2") (pinfunction "2_2") (pintype "passive"))
    )
    (net (code "28") (name "GND") (class "Default")
      (node (ref "C24") (pin "1") (pinfunction "1_1") (pintype "passive"))
      (node (ref "C25") (pin "1") (pinfunction "1_1") (pintype "passive"))
      (node (ref "C27") (pin "1") (pinfunction "1_1") (pintype "passive"))
      (node (ref "C28") (pin "1") (pinfunction "1_1") (pintype "passive"))
      (node (ref "C31") (pin "1") (pinfunction "1_1") (pintype "passive"))
      (node (ref "C32") (pin "1") (pinfunction "1_1") (pintype "passive"))
      (node (ref "C35") (pin "2") (pinfunction "2_2") (pintype "passive"))
      (node (ref "C37") (pin "2") (pinfunction "2_2") (pintype "passive"))
      (node (ref "C38") (pin "2") (pinfunction "2_2") (pintype "passive"))
      (node (ref "C41") (pin "1") (pinfunction "1_1") (pintype "passive"))
      (node (ref "C42") (pin "1") (pinfunction "1_1") (pintype "passive"))
      (node (ref "C441") (pin "1") (pinfunction "1_1") (pintype "passive"))
      (node (ref "C442") (pin "1") (pinfunction "1_1") (pintype "passive"))
      (node (ref "C443") (pin "1") (pinfunction "1_1") (pintype "passive"))
      (node (ref "IC1") (pin "AJ7") (pinfunction "rfsn_l_RFE_2_AJ7") (pintype "passive"))
      (node (ref "IC1") (pin "AJ9") (pinfunction "rfsp_l_RFE_2_AJ9") (pintype "passive"))
      (node (ref "IC42") (pin "2") (pinfunction "GND_2") (pintype "passive"))
      (node (ref "IC43") (pin "2") (pinfunction "GND_2") (pintype "passive"))
      (node (ref "IC44") (pin "2") (pinfunction "GND_2") (pintype "power_in"))
      (node (ref "IC6") (pin "2") (pinfunction "GND_2") (pintype "passive"))
      (node (ref "IC7") (pin "2") (pinfunction "GND_2") (pintype "passive"))
      (node (ref "J10") (pin "2") (pinfunction "Y_2") (pintype "passive"))
      (node (ref "J6") (pin "2") (pinfunction "Y_2") (pintype "passive"))
      (node (ref "J7") (pin "2") (pinfunction "Y_2") (pintype "passive"))
      (node (ref "J8") (pin "2") (pinfunction "Y_2") (pintype "passive"))
      (node (ref "J9") (pin "2") (pinfunction "Y_2") (pintype "passive"))
      (node (ref "RA7") (pin "1") (pinfunction "1_1") (pintype "passive"))
      (node (ref "RA8") (pin "1") (pinfunction "1_1") (pintype "passive"))
      (node (ref "T10") (pin "2") (pinfunction "2_2") (pintype "passive"))
      (node (ref "T10") (pin "4") (pinfunction "4_4") (pintype "passive"))
      (node (ref "T6") (pin "2") (pinfunction "2_2") (pintype "passive"))
      (node (ref "T6") (pin "6") (pinfunction "6_6") (pintype "passive"))
      (node (ref "T7") (pin "3") (pinfunction "3_3") (pintype "passive"))
      (node (ref "T8") (pin "2") (pinfunction "2_2") (pintype "passive"))
      (node (ref "T8") (pin "4") (pinfunction "4_4") (pintype "passive"))
      (node (ref "T9") (pin "2") (pinfunction "2_2") (pintype "passive"))
      (node (ref "VT5") (pin "1") (pinfunction "S_1") (pintype "passive"))
      (node (ref "VT6") (pin "1") (pinfunction "S_1") (pintype "passive"))
    )
    (net (code "29") (name "Net-(C26-Pad2)") (class "Default")
      (node (ref "C26") (pin "2") (pinfunction "2_2") (pintype "passive"))
      (node (ref "T6") (pin "4") (pinfunction "4_4") (pintype "passive"))
    )
    (net (code "30") (name "Net-(C30-Pad2)") (class "Default")
      (node (ref "C30") (pin "2") (pinfunction "2_2") (pintype "passive"))
      (node (ref "T7") (pin "2") (pinfunction "2_2") (pintype "passive"))
    )
    (net (code "31") (name "Net-(C34-Pad2)") (class "Default")
      (node (ref "C34") (pin "2") (pinfunction "2_2") (pintype "passive"))
      (node (ref "T8") (pin "6") (pinfunction "6_6") (pintype "passive"))
    )
    (net (code "32") (name "Net-(C39-Pad2)") (class "Default")
      (node (ref "C39") (pin "2") (pinfunction "2_2") (pintype "passive"))
      (node (ref "T9") (pin "3") (pinfunction "3_3") (pintype "passive"))
    )
    (net (code "33") (name "Net-(C43-Pad2)") (class "Default")
      (node (ref "C43") (pin "2") (pinfunction "2_2") (pintype "passive"))
      (node (ref "T10") (pin "6") (pinfunction "6_6") (pintype "passive"))
    )
    (net (code "34") (name "Net-(IC6-RF_IN)") (class "Default")
      (node (ref "C30") (pin "1") (pinfunction "1_1") (pintype "passive"))
      (node (ref "IC6") (pin "5") (pinfunction "RF_IN_5") (pintype "input"))
    )
    (net (code "35") (name "Net-(IC6-RF_OUT1)") (class "Default")
      (node (ref "C29") (pin "2") (pinfunction "2_2") (pintype "passive"))
      (node (ref "IC6") (pin "1") (pinfunction "RF_OUT1_1") (pintype "output"))
    )
    (net (code "36") (name "Net-(IC6-RF_OUT2)") (class "Default")
      (node (ref "C33") (pin "1") (pinfunction "1_1") (pintype "passive"))
      (node (ref "IC6") (pin "3") (pinfunction "RF_OUT2_3") (pintype "output"))
    )
    (net (code "37") (name "Net-(IC7-RF_IN)") (class "Default")
      (node (ref "C39") (pin "1") (pinfunction "1_1") (pintype "passive"))
      (node (ref "IC7") (pin "5") (pinfunction "RF_IN_5") (pintype "input"))
    )
    (net (code "38") (name "Net-(IC7-RF_OUT1)") (class "Default")
      (node (ref "C36") (pin "2") (pinfunction "2_2") (pintype "passive"))
      (node (ref "IC7") (pin "1") (pinfunction "RF_OUT1_1") (pintype "output"))
    )
    (net (code "39") (name "Net-(IC7-RF_OUT2)") (class "Default")
      (node (ref "C40") (pin "2") (pinfunction "2_2") (pintype "passive"))
      (node (ref "IC7") (pin "3") (pinfunction "RF_OUT2_3") (pintype "output"))
    )
    (net (code "40") (name "Net-(IC42-J1)") (class "Default")
      (node (ref "C445") (pin "2") (pinfunction "2_2") (pintype "passive"))
      (node (ref "IC42") (pin "5") (pinfunction "J1_5") (pintype "passive"))
    )
    (net (code "41") (name "Net-(IC42-J2)") (class "Default")
      (node (ref "C29") (pin "1") (pinfunction "1_1") (pintype "passive"))
      (node (ref "IC42") (pin "3") (pinfunction "J2_3") (pintype "passive"))
    )
    (net (code "42") (name "Net-(IC42-J3)") (class "Default")
      (node (ref "C26") (pin "1") (pinfunction "1_1") (pintype "passive"))
      (node (ref "IC42") (pin "1") (pinfunction "J3_1") (pintype "passive"))
    )
    (net (code "43") (name "Net-(IC43-J1)") (class "Default")
      (node (ref "C446") (pin "1") (pinfunction "1_1") (pintype "passive"))
      (node (ref "IC43") (pin "5") (pinfunction "J1_5") (pintype "passive"))
    )
    (net (code "44") (name "Net-(IC43-J2)") (class "Default")
      (node (ref "C444") (pin "2") (pinfunction "2_2") (pintype "passive"))
      (node (ref "IC43") (pin "3") (pinfunction "J2_3") (pintype "passive"))
    )
    (net (code "45") (name "Net-(IC43-J3)") (class "Default")
      (node (ref "C447") (pin "2") (pinfunction "2_2") (pintype "passive"))
      (node (ref "IC43") (pin "1") (pinfunction "J3_1") (pintype "passive"))
    )
    (net (code "46") (name "Net-(IC44-RFIN)") (class "Default")
      (node (ref "C445") (pin "1") (pinfunction "1_1") (pintype "passive"))
      (node (ref "IC44") (pin "1") (pinfunction "RFIN_1") (pintype "input"))
    )
    (net (code "47") (name "Net-(IC44-RFOUT)") (class "Default")
      (node (ref "C446") (pin "2") (pinfunction "2_2") (pintype "passive"))
      (node (ref "IC44") (pin "3") (pinfunction "RFOUT_3") (pintype "output"))
      (node (ref "MN58") (pin "1") (pinfunction "1_1") (pintype "passive"))
    )
    (net (code "48") (name "Net-(J6-X)") (class "Default")
      (node (ref "C444") (pin "1") (pinfunction "1_1") (pintype "passive"))
      (node (ref "J6") (pin "1") (pinfunction "X_1") (pintype "passive"))
    )
    (net (code "49") (name "Net-(J7-X)") (class "Default")
      (node (ref "C447") (pin "1") (pinfunction "1_1") (pintype "passive"))
      (node (ref "J7") (pin "1") (pinfunction "X_1") (pintype "passive"))
    )
    (net (code "50") (name "Net-(J8-X)") (class "Default")
      (node (ref "C34") (pin "1") (pinfunction "1_1") (pintype "passive"))
      (node (ref "J8") (pin "1") (pinfunction "X_1") (pintype "passive"))
    )
    (net (code "51") (name "Net-(J9-X)") (class "Default")
      (node (ref "C40") (pin "1") (pinfunction "1_1") (pintype "passive"))
      (node (ref "J9") (pin "1") (pinfunction "X_1") (pintype "passive"))
    )
    (net (code "52") (name "Net-(J10-X)") (class "Default")
      (node (ref "C43") (pin "1") (pinfunction "1_1") (pintype "passive"))
      (node (ref "J10") (pin "1") (pinfunction "X_1") (pintype "passive"))
    )
    (net (code "53") (name "Net-(MN29-Pad1)") (class "Default")
      (node (ref "MN29") (pin "1") (pinfunction "1_1") (pintype "passive"))
      (node (ref "MN31") (pin "2") (pinfunction "2_2") (pintype "passive"))
    )
    (net (code "54") (name "Net-(MN30-Pad1)") (class "Default")
      (node (ref "MN30") (pin "1") (pinfunction "1_1") (pintype "passive"))
      (node (ref "MN32") (pin "2") (pinfunction "2_2") (pintype "passive"))
    )
    (net (code "55") (name "Net-(MN37-Pad1)") (class "Default")
      (node (ref "MN37") (pin "1") (pinfunction "1_1") (pintype "passive"))
      (node (ref "MN39") (pin "2") (pinfunction "2_2") (pintype "passive"))
    )
    (net (code "56") (name "Net-(MN38-Pad1)") (class "Default")
      (node (ref "MN38") (pin "1") (pinfunction "1_1") (pintype "passive"))
      (node (ref "MN40") (pin "2") (pinfunction "2_2") (pintype "passive"))
    )
    (net (code "57") (name "Net-(VT4-D)") (class "Default")
      (node (ref "RA5") (pin "2") (pinfunction "2_2") (pintype "passive"))
      (node (ref "VT4") (pin "2") (pinfunction "D_2") (pintype "passive"))
    )
    (net (code "58") (name "Net-(VT4-G1)") (class "Default")
      (node (ref "R18") (pin "1") (pinfunction "1_1") (pintype "passive"))
      (node (ref "VT4") (pin "3") (pinfunction "G2_3") (pintype "passive"))
      (node (ref "VT4") (pin "4") (pinfunction "G1_4") (pintype "passive"))
    )
    (net (code "59") (name "Net-(VT4-S)") (class "Default")
      (node (ref "C33") (pin "2") (pinfunction "2_2") (pintype "passive"))
      (node (ref "R19") (pin "1") (pinfunction "1_1") (pintype "passive"))
      (node (ref "RA6") (pin "1") (pinfunction "1_1") (pintype "passive"))
      (node (ref "RA7") (pin "2") (pinfunction "2_2") (pintype "passive"))
      (node (ref "VT4") (pin "1") (pinfunction "S_1") (pintype "passive"))
      (node (ref "VT6") (pin "2") (pinfunction "D_2") (pintype "passive"))
    )
    (net (code "60") (name "Net-(VT5-D)") (class "Default")
      (node (ref "C36") (pin "1") (pinfunction "1_1") (pintype "passive"))
      (node (ref "RA5") (pin "1") (pinfunction "1_1") (pintype "passive"))
      (node (ref "RA6") (pin "2") (pinfunction "2_2") (pintype "passive"))
      (node (ref "RA8") (pin "2") (pinfunction "2_2") (pintype "passive"))
      (node (ref "VT5") (pin "2") (pinfunction "D_2") (pintype "passive"))
    )
    (net (code "61") (name "Net-(VT5-G1)") (class "Default")
      (node (ref "R20") (pin "2") (pinfunction "2_2") (pintype "passive"))
      (node (ref "VT5") (pin "3") (pinfunction "G2_3") (pintype "passive"))
      (node (ref "VT5") (pin "4") (pinfunction "G1_4") (pintype "passive"))
    )
    (net (code "62") (name "Net-(VT6-G1)") (class "Default")
      (node (ref "R21") (pin "1") (pinfunction "1_1") (pintype "passive"))
      (node (ref "VT6") (pin "3") (pinfunction "G2_3") (pintype "passive"))
      (node (ref "VT6") (pin "4") (pinfunction "G1_4") (pintype "passive"))
    )
    (net (code "63") (name "VCC1P8_LMS") (class "Default")
      (node (ref "C24") (pin "2") (pinfunction "2_2") (pintype "passive"))
      (node (ref "C25") (pin "2") (pinfunction "2_2") (pintype "passive"))
      (node (ref "C27") (pin "2") (pinfunction "2_2") (pintype "passive"))
      (node (ref "C28") (pin "2") (pinfunction "2_2") (pintype "passive"))
      (node (ref "MN29") (pin "2") (pinfunction "2_2") (pintype "passive"))
      (node (ref "MN30") (pin "2") (pinfunction "2_2") (pintype "passive"))
      (node (ref "MN37") (pin "2") (pinfunction "2_2") (pintype "passive"))
      (node (ref "MN38") (pin "2") (pinfunction "2_2") (pintype "passive"))
      (node (ref "R19") (pin "2") (pinfunction "2_2") (pintype "passive"))
    )
  )
)
